# placa_para_insolar_joystick.net
KiCad netlist of a schematic drawn in EAGLE
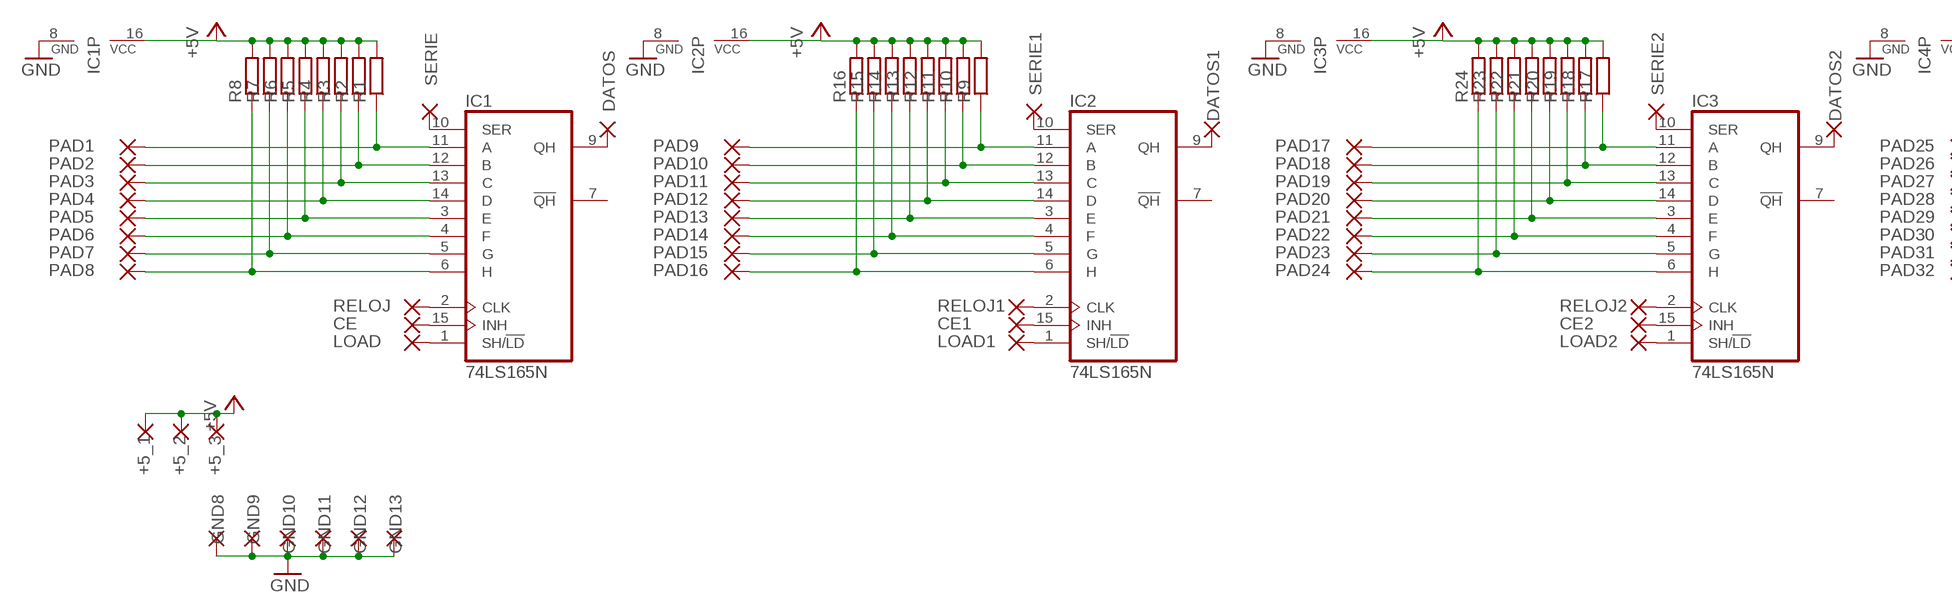
[diagram p0: schematic, sheet 1, part 1 of 2]
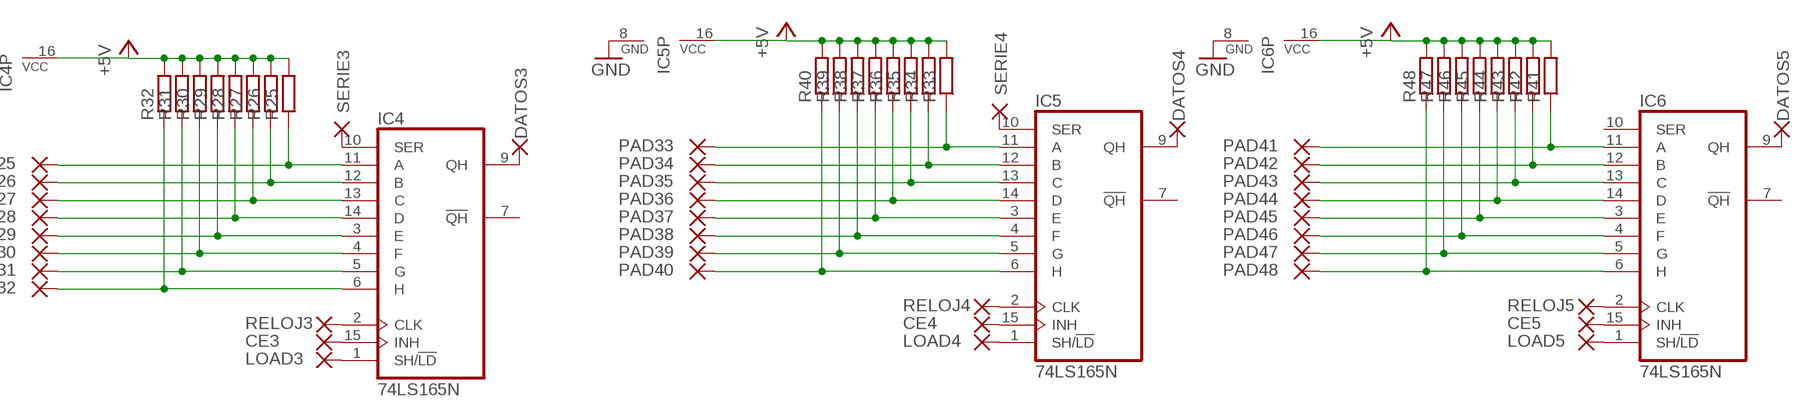
[diagram p1: schematic, sheet 1, part 2 of 2]

(export (version "E")
  (design (tool "Eeschema 10.0.6"))
  (components
    (comp (ref "+5_1")
      (value "WIREPAD2,54/1,0")
      (footprint "eagle-import:2,54_1,0")
      (libsource (lib "eagle-import") (part "WIREPAD2,54/1,0"))
    )
    (comp (ref "+5_2")
      (value "WIREPAD2,54/1,0")
      (footprint "eagle-import:2,54_1,0")
      (libsource (lib "eagle-import") (part "WIREPAD2,54/1,0"))
    )
    (comp (ref "+5_3")
      (value "WIREPAD2,54/1,0")
      (footprint "eagle-import:2,54_1,0")
      (libsource (lib "eagle-import") (part "WIREPAD2,54/1,0"))
    )
    (comp (ref "CE")
      (value "WIREPAD2,54/1,0")
      (footprint "eagle-import:2,54_1,0")
      (libsource (lib "eagle-import") (part "WIREPAD2,54/1,0"))
    )
    (comp (ref "CE1")
      (value "WIREPAD2,54/1,0")
      (footprint "eagle-import:2,54_1,0")
      (libsource (lib "eagle-import") (part "WIREPAD2,54/1,0"))
    )
    (comp (ref "CE2")
      (value "WIREPAD2,54/1,0")
      (footprint "eagle-import:2,54_1,0")
      (libsource (lib "eagle-import") (part "WIREPAD2,54/1,0"))
    )
    (comp (ref "CE3")
      (value "WIREPAD2,54/1,0")
      (footprint "eagle-import:2,54_1,0")
      (libsource (lib "eagle-import") (part "WIREPAD2,54/1,0"))
    )
    (comp (ref "CE4")
      (value "WIREPAD2,54/1,0")
      (footprint "eagle-import:2,54_1,0")
      (libsource (lib "eagle-import") (part "WIREPAD2,54/1,0"))
    )
    (comp (ref "CE5")
      (value "WIREPAD2,54/1,0")
      (footprint "eagle-import:2,54_1,0")
      (libsource (lib "eagle-import") (part "WIREPAD2,54/1,0"))
    )
    (comp (ref "DATOS")
      (value "WIREPAD2,54/1,0")
      (footprint "eagle-import:2,54_1,0")
      (libsource (lib "eagle-import") (part "WIREPAD2,54/1,0"))
    )
    (comp (ref "DATOS1")
      (value "WIREPAD2,54/1,0")
      (footprint "eagle-import:2,54_1,0")
      (libsource (lib "eagle-import") (part "WIREPAD2,54/1,0"))
    )
    (comp (ref "DATOS2")
      (value "WIREPAD2,54/1,0")
      (footprint "eagle-import:2,54_1,0")
      (libsource (lib "eagle-import") (part "WIREPAD2,54/1,0"))
    )
    (comp (ref "DATOS3")
      (value "WIREPAD2,54/1,0")
      (footprint "eagle-import:2,54_1,0")
      (libsource (lib "eagle-import") (part "WIREPAD2,54/1,0"))
    )
    (comp (ref "DATOS4")
      (value "WIREPAD2,54/1,0")
      (footprint "eagle-import:2,54_1,0")
      (libsource (lib "eagle-import") (part "WIREPAD2,54/1,0"))
    )
    (comp (ref "DATOS5")
      (value "WIREPAD2,54/1,0")
      (footprint "eagle-import:2,54_1,0")
      (libsource (lib "eagle-import") (part "WIREPAD2,54/1,0"))
    )
    (comp (ref "GND8")
      (value "WIREPAD2,54/1,0")
      (footprint "eagle-import:2,54_1,0")
      (libsource (lib "eagle-import") (part "WIREPAD2,54/1,0"))
    )
    (comp (ref "GND9")
      (value "WIREPAD2,54/1,0")
      (footprint "eagle-import:2,54_1,0")
      (libsource (lib "eagle-import") (part "WIREPAD2,54/1,0"))
    )
    (comp (ref "GND10")
      (value "WIREPAD2,54/1,0")
      (footprint "eagle-import:2,54_1,0")
      (libsource (lib "eagle-import") (part "WIREPAD2,54/1,0"))
    )
    (comp (ref "GND11")
      (value "WIREPAD2,54/1,0")
      (footprint "eagle-import:2,54_1,0")
      (libsource (lib "eagle-import") (part "WIREPAD2,54/1,0"))
    )
    (comp (ref "GND12")
      (value "WIREPAD2,54/1,0")
      (footprint "eagle-import:2,54_1,0")
      (libsource (lib "eagle-import") (part "WIREPAD2,54/1,0"))
    )
    (comp (ref "GND13")
      (value "WIREPAD2,54/1,0")
      (footprint "eagle-import:2,54_1,0")
      (libsource (lib "eagle-import") (part "WIREPAD2,54/1,0"))
    )
    (comp (ref "IC1")
      (value "74LS165N")
      (footprint "eagle-import:DIL16")
      (libsource (lib "eagle-import") (part "74165NLS"))
    )
    (comp (ref "IC2")
      (value "74LS165N")
      (footprint "eagle-import:DIL16")
      (libsource (lib "eagle-import") (part "74165NLS"))
    )
    (comp (ref "IC3")
      (value "74LS165N")
      (footprint "eagle-import:DIL16")
      (libsource (lib "eagle-import") (part "74165NLS"))
    )
    (comp (ref "IC4")
      (value "74LS165N")
      (footprint "eagle-import:DIL16")
      (libsource (lib "eagle-import") (part "74165NLS"))
    )
    (comp (ref "IC5")
      (value "74LS165N")
      (footprint "eagle-import:DIL16")
      (libsource (lib "eagle-import") (part "74165NLS"))
    )
    (comp (ref "IC6")
      (value "74LS165N")
      (footprint "eagle-import:DIL16")
      (libsource (lib "eagle-import") (part "74165NLS"))
    )
    (comp (ref "LOAD")
      (value "WIREPAD2,54/1,0")
      (footprint "eagle-import:2,54_1,0")
      (libsource (lib "eagle-import") (part "WIREPAD2,54/1,0"))
    )
    (comp (ref "LOAD1")
      (value "WIREPAD2,54/1,0")
      (footprint "eagle-import:2,54_1,0")
      (libsource (lib "eagle-import") (part "WIREPAD2,54/1,0"))
    )
    (comp (ref "LOAD2")
      (value "WIREPAD2,54/1,0")
      (footprint "eagle-import:2,54_1,0")
      (libsource (lib "eagle-import") (part "WIREPAD2,54/1,0"))
    )
    (comp (ref "LOAD3")
      (value "WIREPAD2,54/1,0")
      (footprint "eagle-import:2,54_1,0")
      (libsource (lib "eagle-import") (part "WIREPAD2,54/1,0"))
    )
    (comp (ref "LOAD4")
      (value "WIREPAD2,54/1,0")
      (footprint "eagle-import:2,54_1,0")
      (libsource (lib "eagle-import") (part "WIREPAD2,54/1,0"))
    )
    (comp (ref "LOAD5")
      (value "WIREPAD2,54/1,0")
      (footprint "eagle-import:2,54_1,0")
      (libsource (lib "eagle-import") (part "WIREPAD2,54/1,0"))
    )
    (comp (ref "PAD1")
      (value "WIREPAD2,54/1,0")
      (footprint "eagle-import:2,54_1,0")
      (libsource (lib "eagle-import") (part "WIREPAD2,54/1,0"))
    )
    (comp (ref "PAD2")
      (value "WIREPAD2,54/1,0")
      (footprint "eagle-import:2,54_1,0")
      (libsource (lib "eagle-import") (part "WIREPAD2,54/1,0"))
    )
    (comp (ref "PAD3")
      (value "WIREPAD2,54/1,0")
      (footprint "eagle-import:2,54_1,0")
      (libsource (lib "eagle-import") (part "WIREPAD2,54/1,0"))
    )
    (comp (ref "PAD4")
      (value "WIREPAD2,54/1,0")
      (footprint "eagle-import:2,54_1,0")
      (libsource (lib "eagle-import") (part "WIREPAD2,54/1,0"))
    )
    (comp (ref "PAD5")
      (value "WIREPAD2,54/1,0")
      (footprint "eagle-import:2,54_1,0")
      (libsource (lib "eagle-import") (part "WIREPAD2,54/1,0"))
    )
    (comp (ref "PAD6")
      (value "WIREPAD2,54/1,0")
      (footprint "eagle-import:2,54_1,0")
      (libsource (lib "eagle-import") (part "WIREPAD2,54/1,0"))
    )
    (comp (ref "PAD7")
      (value "WIREPAD2,54/1,0")
      (footprint "eagle-import:2,54_1,0")
      (libsource (lib "eagle-import") (part "WIREPAD2,54/1,0"))
    )
    (comp (ref "PAD8")
      (value "WIREPAD2,54/1,0")
      (footprint "eagle-import:2,54_1,0")
      (libsource (lib "eagle-import") (part "WIREPAD2,54/1,0"))
    )
    (comp (ref "PAD9")
      (value "WIREPAD2,54/1,0")
      (footprint "eagle-import:2,54_1,0")
      (libsource (lib "eagle-import") (part "WIREPAD2,54/1,0"))
    )
    (comp (ref "PAD10")
      (value "WIREPAD2,54/1,0")
      (footprint "eagle-import:2,54_1,0")
      (libsource (lib "eagle-import") (part "WIREPAD2,54/1,0"))
    )
    (comp (ref "PAD11")
      (value "WIREPAD2,54/1,0")
      (footprint "eagle-import:2,54_1,0")
      (libsource (lib "eagle-import") (part "WIREPAD2,54/1,0"))
    )
    (comp (ref "PAD12")
      (value "WIREPAD2,54/1,0")
      (footprint "eagle-import:2,54_1,0")
      (libsource (lib "eagle-import") (part "WIREPAD2,54/1,0"))
    )
    (comp (ref "PAD13")
      (value "WIREPAD2,54/1,0")
      (footprint "eagle-import:2,54_1,0")
      (libsource (lib "eagle-import") (part "WIREPAD2,54/1,0"))
    )
    (comp (ref "PAD14")
      (value "WIREPAD2,54/1,0")
      (footprint "eagle-import:2,54_1,0")
      (libsource (lib "eagle-import") (part "WIREPAD2,54/1,0"))
    )
    (comp (ref "PAD15")
      (value "WIREPAD2,54/1,0")
      (footprint "eagle-import:2,54_1,0")
      (libsource (lib "eagle-import") (part "WIREPAD2,54/1,0"))
    )
    (comp (ref "PAD16")
      (value "WIREPAD2,54/1,0")
      (footprint "eagle-import:2,54_1,0")
      (libsource (lib "eagle-import") (part "WIREPAD2,54/1,0"))
    )
    (comp (ref "PAD17")
      (value "WIREPAD2,54/1,0")
      (footprint "eagle-import:2,54_1,0")
      (libsource (lib "eagle-import") (part "WIREPAD2,54/1,0"))
    )
    (comp (ref "PAD18")
      (value "WIREPAD2,54/1,0")
      (footprint "eagle-import:2,54_1,0")
      (libsource (lib "eagle-import") (part "WIREPAD2,54/1,0"))
    )
    (comp (ref "PAD19")
      (value "WIREPAD2,54/1,0")
      (footprint "eagle-import:2,54_1,0")
      (libsource (lib "eagle-import") (part "WIREPAD2,54/1,0"))
    )
    (comp (ref "PAD20")
      (value "WIREPAD2,54/1,0")
      (footprint "eagle-import:2,54_1,0")
      (libsource (lib "eagle-import") (part "WIREPAD2,54/1,0"))
    )
    (comp (ref "PAD21")
      (value "WIREPAD2,54/1,0")
      (footprint "eagle-import:2,54_1,0")
      (libsource (lib "eagle-import") (part "WIREPAD2,54/1,0"))
    )
    (comp (ref "PAD22")
      (value "WIREPAD2,54/1,0")
      (footprint "eagle-import:2,54_1,0")
      (libsource (lib "eagle-import") (part "WIREPAD2,54/1,0"))
    )
    (comp (ref "PAD23")
      (value "WIREPAD2,54/1,0")
      (footprint "eagle-import:2,54_1,0")
      (libsource (lib "eagle-import") (part "WIREPAD2,54/1,0"))
    )
    (comp (ref "PAD24")
      (value "WIREPAD2,54/1,0")
      (footprint "eagle-import:2,54_1,0")
      (libsource (lib "eagle-import") (part "WIREPAD2,54/1,0"))
    )
    (comp (ref "PAD25")
      (value "WIREPAD2,54/1,0")
      (footprint "eagle-import:2,54_1,0")
      (libsource (lib "eagle-import") (part "WIREPAD2,54/1,0"))
    )
    (comp (ref "PAD26")
      (value "WIREPAD2,54/1,0")
      (footprint "eagle-import:2,54_1,0")
      (libsource (lib "eagle-import") (part "WIREPAD2,54/1,0"))
    )
    (comp (ref "PAD27")
      (value "WIREPAD2,54/1,0")
      (footprint "eagle-import:2,54_1,0")
      (libsource (lib "eagle-import") (part "WIREPAD2,54/1,0"))
    )
    (comp (ref "PAD28")
      (value "WIREPAD2,54/1,0")
      (footprint "eagle-import:2,54_1,0")
      (libsource (lib "eagle-import") (part "WIREPAD2,54/1,0"))
    )
    (comp (ref "PAD29")
      (value "WIREPAD2,54/1,0")
      (footprint "eagle-import:2,54_1,0")
      (libsource (lib "eagle-import") (part "WIREPAD2,54/1,0"))
    )
    (comp (ref "PAD30")
      (value "WIREPAD2,54/1,0")
      (footprint "eagle-import:2,54_1,0")
      (libsource (lib "eagle-import") (part "WIREPAD2,54/1,0"))
    )
    (comp (ref "PAD31")
      (value "WIREPAD2,54/1,0")
      (footprint "eagle-import:2,54_1,0")
      (libsource (lib "eagle-import") (part "WIREPAD2,54/1,0"))
    )
    (comp (ref "PAD32")
      (value "WIREPAD2,54/1,0")
      (footprint "eagle-import:2,54_1,0")
      (libsource (lib "eagle-import") (part "WIREPAD2,54/1,0"))
    )
    (comp (ref "PAD33")
      (value "WIREPAD2,54/1,0")
      (footprint "eagle-import:2,54_1,0")
      (libsource (lib "eagle-import") (part "WIREPAD2,54/1,0"))
    )
    (comp (ref "PAD34")
      (value "WIREPAD2,54/1,0")
      (footprint "eagle-import:2,54_1,0")
      (libsource (lib "eagle-import") (part "WIREPAD2,54/1,0"))
    )
    (comp (ref "PAD35")
      (value "WIREPAD2,54/1,0")
      (footprint "eagle-import:2,54_1,0")
      (libsource (lib "eagle-import") (part "WIREPAD2,54/1,0"))
    )
    (comp (ref "PAD36")
      (value "WIREPAD2,54/1,0")
      (footprint "eagle-import:2,54_1,0")
      (libsource (lib "eagle-import") (part "WIREPAD2,54/1,0"))
    )
    (comp (ref "PAD37")
      (value "WIREPAD2,54/1,0")
      (footprint "eagle-import:2,54_1,0")
      (libsource (lib "eagle-import") (part "WIREPAD2,54/1,0"))
    )
    (comp (ref "PAD38")
      (value "WIREPAD2,54/1,0")
      (footprint "eagle-import:2,54_1,0")
      (libsource (lib "eagle-import") (part "WIREPAD2,54/1,0"))
    )
    (comp (ref "PAD39")
      (value "WIREPAD2,54/1,0")
      (footprint "eagle-import:2,54_1,0")
      (libsource (lib "eagle-import") (part "WIREPAD2,54/1,0"))
    )
    (comp (ref "PAD40")
      (value "WIREPAD2,54/1,0")
      (footprint "eagle-import:2,54_1,0")
      (libsource (lib "eagle-import") (part "WIREPAD2,54/1,0"))
    )
    (comp (ref "PAD41")
      (value "WIREPAD2,54/1,0")
      (footprint "eagle-import:2,54_1,0")
      (libsource (lib "eagle-import") (part "WIREPAD2,54/1,0"))
    )
    (comp (ref "PAD42")
      (value "WIREPAD2,54/1,0")
      (footprint "eagle-import:2,54_1,0")
      (libsource (lib "eagle-import") (part "WIREPAD2,54/1,0"))
    )
    (comp (ref "PAD43")
      (value "WIREPAD2,54/1,0")
      (footprint "eagle-import:2,54_1,0")
      (libsource (lib "eagle-import") (part "WIREPAD2,54/1,0"))
    )
    (comp (ref "PAD44")
      (value "WIREPAD2,54/1,0")
      (footprint "eagle-import:2,54_1,0")
      (libsource (lib "eagle-import") (part "WIREPAD2,54/1,0"))
    )
    (comp (ref "PAD45")
      (value "WIREPAD2,54/1,0")
      (footprint "eagle-import:2,54_1,0")
      (libsource (lib "eagle-import") (part "WIREPAD2,54/1,0"))
    )
    (comp (ref "PAD46")
      (value "WIREPAD2,54/1,0")
      (footprint "eagle-import:2,54_1,0")
      (libsource (lib "eagle-import") (part "WIREPAD2,54/1,0"))
    )
    (comp (ref "PAD47")
      (value "WIREPAD2,54/1,0")
      (footprint "eagle-import:2,54_1,0")
      (libsource (lib "eagle-import") (part "WIREPAD2,54/1,0"))
    )
    (comp (ref "PAD48")
      (value "WIREPAD2,54/1,0")
      (footprint "eagle-import:2,54_1,0")
      (libsource (lib "eagle-import") (part "WIREPAD2,54/1,0"))
    )
    (comp (ref "R1")
      (value "R-EU_0204/7")
      (footprint "eagle-import:0204_7")
      (libsource (lib "eagle-import") (part "R-EU_0204/7"))
    )
    (comp (ref "R2")
      (value "R-EU_0204/7")
      (footprint "eagle-import:0204_7")
      (libsource (lib "eagle-import") (part "R-EU_0204/7"))
    )
    (comp (ref "R3")
      (value "R-EU_0204/7")
      (footprint "eagle-import:0204_7")
      (libsource (lib "eagle-import") (part "R-EU_0204/7"))
    )
    (comp (ref "R4")
      (value "R-EU_0204/7")
      (footprint "eagle-import:0204_7")
      (libsource (lib "eagle-import") (part "R-EU_0204/7"))
    )
    (comp (ref "R5")
      (value "R-EU_0204/7")
      (footprint "eagle-import:0204_7")
      (libsource (lib "eagle-import") (part "R-EU_0204/7"))
    )
    (comp (ref "R6")
      (value "R-EU_0204/7")
      (footprint "eagle-import:0204_7")
      (libsource (lib "eagle-import") (part "R-EU_0204/7"))
    )
    (comp (ref "R7")
      (value "R-EU_0204/7")
      (footprint "eagle-import:0204_7")
      (libsource (lib "eagle-import") (part "R-EU_0204/7"))
    )
    (comp (ref "R8")
      (value "R-EU_0204/7")
      (footprint "eagle-import:0204_7")
      (libsource (lib "eagle-import") (part "R-EU_0204/7"))
    )
    (comp (ref "R9")
      (value "R-EU_0204/7")
      (footprint "eagle-import:0204_7")
      (libsource (lib "eagle-import") (part "R-EU_0204/7"))
    )
    (comp (ref "R10")
      (value "R-EU_0204/7")
      (footprint "eagle-import:0204_7")
      (libsource (lib "eagle-import") (part "R-EU_0204/7"))
    )
    (comp (ref "R11")
      (value "R-EU_0204/7")
      (footprint "eagle-import:0204_7")
      (libsource (lib "eagle-import") (part "R-EU_0204/7"))
    )
    (comp (ref "R12")
      (value "R-EU_0204/7")
      (footprint "eagle-import:0204_7")
      (libsource (lib "eagle-import") (part "R-EU_0204/7"))
    )
    (comp (ref "R13")
      (value "R-EU_0204/7")
      (footprint "eagle-import:0204_7")
      (libsource (lib "eagle-import") (part "R-EU_0204/7"))
    )
    (comp (ref "R14")
      (value "R-EU_0204/7")
      (footprint "eagle-import:0204_7")
      (libsource (lib "eagle-import") (part "R-EU_0204/7"))
    )
    (comp (ref "R15")
      (value "R-EU_0204/7")
      (footprint "eagle-import:0204_7")
      (libsource (lib "eagle-import") (part "R-EU_0204/7"))
    )
    (comp (ref "R16")
      (value "R-EU_0204/7")
      (footprint "eagle-import:0204_7")
      (libsource (lib "eagle-import") (part "R-EU_0204/7"))
    )
    (comp (ref "R17")
      (value "R-EU_0204/7")
      (footprint "eagle-import:0204_7")
      (libsource (lib "eagle-import") (part "R-EU_0204/7"))
    )
    (comp (ref "R18")
      (value "R-EU_0204/7")
      (footprint "eagle-import:0204_7")
      (libsource (lib "eagle-import") (part "R-EU_0204/7"))
    )
    (comp (ref "R19")
      (value "R-EU_0204/7")
      (footprint "eagle-import:0204_7")
      (libsource (lib "eagle-import") (part "R-EU_0204/7"))
    )
    (comp (ref "R20")
      (value "R-EU_0204/7")
      (footprint "eagle-import:0204_7")
      (libsource (lib "eagle-import") (part "R-EU_0204/7"))
    )
    (comp (ref "R21")
      (value "R-EU_0204/7")
      (footprint "eagle-import:0204_7")
      (libsource (lib "eagle-import") (part "R-EU_0204/7"))
    )
    (comp (ref "R22")
      (value "R-EU_0204/7")
      (footprint "eagle-import:0204_7")
      (libsource (lib "eagle-import") (part "R-EU_0204/7"))
    )
    (comp (ref "R23")
      (value "R-EU_0204/7")
      (footprint "eagle-import:0204_7")
      (libsource (lib "eagle-import") (part "R-EU_0204/7"))
    )
    (comp (ref "R24")
      (value "R-EU_0204/7")
      (footprint "eagle-import:0204_7")
      (libsource (lib "eagle-import") (part "R-EU_0204/7"))
    )
    (comp (ref "R25")
      (value "R-EU_0204/7")
      (footprint "eagle-import:0204_7")
      (libsource (lib "eagle-import") (part "R-EU_0204/7"))
    )
    (comp (ref "R26")
      (value "R-EU_0204/7")
      (footprint "eagle-import:0204_7")
      (libsource (lib "eagle-import") (part "R-EU_0204/7"))
    )
    (comp (ref "R27")
      (value "R-EU_0204/7")
      (footprint "eagle-import:0204_7")
      (libsource (lib "eagle-import") (part "R-EU_0204/7"))
    )
    (comp (ref "R28")
      (value "R-EU_0204/7")
      (footprint "eagle-import:0204_7")
      (libsource (lib "eagle-import") (part "R-EU_0204/7"))
    )
    (comp (ref "R29")
      (value "R-EU_0204/7")
      (footprint "eagle-import:0204_7")
      (libsource (lib "eagle-import") (part "R-EU_0204/7"))
    )
    (comp (ref "R30")
      (value "R-EU_0204/7")
      (footprint "eagle-import:0204_7")
      (libsource (lib "eagle-import") (part "R-EU_0204/7"))
    )
    (comp (ref "R31")
      (value "R-EU_0204/7")
      (footprint "eagle-import:0204_7")
      (libsource (lib "eagle-import") (part "R-EU_0204/7"))
    )
    (comp (ref "R32")
      (value "R-EU_0204/7")
      (footprint "eagle-import:0204_7")
      (libsource (lib "eagle-import") (part "R-EU_0204/7"))
    )
    (comp (ref "R33")
      (value "R-EU_0204/7")
      (footprint "eagle-import:0204_7")
      (libsource (lib "eagle-import") (part "R-EU_0204/7"))
    )
    (comp (ref "R34")
      (value "R-EU_0204/7")
      (footprint "eagle-import:0204_7")
      (libsource (lib "eagle-import") (part "R-EU_0204/7"))
    )
    (comp (ref "R35")
      (value "R-EU_0204/7")
      (footprint "eagle-import:0204_7")
      (libsource (lib "eagle-import") (part "R-EU_0204/7"))
    )
    (comp (ref "R36")
      (value "R-EU_0204/7")
      (footprint "eagle-import:0204_7")
      (libsource (lib "eagle-import") (part "R-EU_0204/7"))
    )
    (comp (ref "R37")
      (value "R-EU_0204/7")
      (footprint "eagle-import:0204_7")
      (libsource (lib "eagle-import") (part "R-EU_0204/7"))
    )
    (comp (ref "R38")
      (value "R-EU_0204/7")
      (footprint "eagle-import:0204_7")
      (libsource (lib "eagle-import") (part "R-EU_0204/7"))
    )
    (comp (ref "R39")
      (value "R-EU_0204/7")
      (footprint "eagle-import:0204_7")
      (libsource (lib "eagle-import") (part "R-EU_0204/7"))
    )
    (comp (ref "R40")
      (value "R-EU_0204/7")
      (footprint "eagle-import:0204_7")
      (libsource (lib "eagle-import") (part "R-EU_0204/7"))
    )
    (comp (ref "R41")
      (value "R-EU_0204/7")
      (footprint "eagle-import:0204_7")
      (libsource (lib "eagle-import") (part "R-EU_0204/7"))
    )
    (comp (ref "R42")
      (value "R-EU_0204/7")
      (footprint "eagle-import:0204_7")
      (libsource (lib "eagle-import") (part "R-EU_0204/7"))
    )
    (comp (ref "R43")
      (value "R-EU_0204/7")
      (footprint "eagle-import:0204_7")
      (libsource (lib "eagle-import") (part "R-EU_0204/7"))
    )
    (comp (ref "R44")
      (value "R-EU_0204/7")
      (footprint "eagle-import:0204_7")
      (libsource (lib "eagle-import") (part "R-EU_0204/7"))
    )
    (comp (ref "R45")
      (value "R-EU_0204/7")
      (footprint "eagle-import:0204_7")
      (libsource (lib "eagle-import") (part "R-EU_0204/7"))
    )
    (comp (ref "R46")
      (value "R-EU_0204/7")
      (footprint "eagle-import:0204_7")
      (libsource (lib "eagle-import") (part "R-EU_0204/7"))
    )
    (comp (ref "R47")
      (value "R-EU_0204/7")
      (footprint "eagle-import:0204_7")
      (libsource (lib "eagle-import") (part "R-EU_0204/7"))
    )
    (comp (ref "R48")
      (value "R-EU_0204/7")
      (footprint "eagle-import:0204_7")
      (libsource (lib "eagle-import") (part "R-EU_0204/7"))
    )
    (comp (ref "RELOJ")
      (value "WIREPAD2,54/1,0")
      (footprint "eagle-import:2,54_1,0")
      (libsource (lib "eagle-import") (part "WIREPAD2,54/1,0"))
    )
    (comp (ref "RELOJ1")
      (value "WIREPAD2,54/1,0")
      (footprint "eagle-import:2,54_1,0")
      (libsource (lib "eagle-import") (part "WIREPAD2,54/1,0"))
    )
    (comp (ref "RELOJ2")
      (value "WIREPAD2,54/1,0")
      (footprint "eagle-import:2,54_1,0")
      (libsource (lib "eagle-import") (part "WIREPAD2,54/1,0"))
    )
    (comp (ref "RELOJ3")
      (value "WIREPAD2,54/1,0")
      (footprint "eagle-import:2,54_1,0")
      (libsource (lib "eagle-import") (part "WIREPAD2,54/1,0"))
    )
    (comp (ref "RELOJ4")
      (value "WIREPAD2,54/1,0")
      (footprint "eagle-import:2,54_1,0")
      (libsource (lib "eagle-import") (part "WIREPAD2,54/1,0"))
    )
    (comp (ref "RELOJ5")
      (value "WIREPAD2,54/1,0")
      (footprint "eagle-import:2,54_1,0")
      (libsource (lib "eagle-import") (part "WIREPAD2,54/1,0"))
    )
    (comp (ref "SERIE")
      (value "WIREPAD2,54/1,0")
      (footprint "eagle-import:2,54_1,0")
      (libsource (lib "eagle-import") (part "WIREPAD2,54/1,0"))
    )
    (comp (ref "SERIE1")
      (value "WIREPAD2,54/1,0")
      (footprint "eagle-import:2,54_1,0")
      (libsource (lib "eagle-import") (part "WIREPAD2,54/1,0"))
    )
    (comp (ref "SERIE2")
      (value "WIREPAD2,54/1,0")
      (footprint "eagle-import:2,54_1,0")
      (libsource (lib "eagle-import") (part "WIREPAD2,54/1,0"))
    )
    (comp (ref "SERIE3")
      (value "WIREPAD2,54/1,0")
      (footprint "eagle-import:2,54_1,0")
      (libsource (lib "eagle-import") (part "WIREPAD2,54/1,0"))
    )
    (comp (ref "SERIE4")
      (value "WIREPAD2,54/1,0")
      (footprint "eagle-import:2,54_1,0")
      (libsource (lib "eagle-import") (part "WIREPAD2,54/1,0"))
    )
  )
  (nets
    (net (code "1") (name "+5V") (class "Default")
      (node (ref "+5_1") (pin "1") (pinfunction "P_1") (pintype "passive"))
      (node (ref "+5_2") (pin "1") (pinfunction "P_1") (pintype "passive"))
      (node (ref "+5_3") (pin "1") (pinfunction "P_1") (pintype "passive"))
      (node (ref "IC1") (pin "16") (pinfunction "VCC_16") (pintype "power_in"))
      (node (ref "IC2") (pin "16") (pinfunction "VCC_16") (pintype "power_in"))
      (node (ref "IC3") (pin "16") (pinfunction "VCC_16") (pintype "power_in"))
      (node (ref "IC4") (pin "16") (pinfunction "VCC_16") (pintype "power_in"))
      (node (ref "IC5") (pin "16") (pinfunction "VCC_16") (pintype "power_in"))
      (node (ref "IC6") (pin "16") (pinfunction "VCC_16") (pintype "power_in"))
      (node (ref "R1") (pin "2") (pinfunction "2_2") (pintype "passive"))
      (node (ref "R10") (pin "2") (pinfunction "2_2") (pintype "passive"))
      (node (ref "R11") (pin "2") (pinfunction "2_2") (pintype "passive"))
      (node (ref "R12") (pin "2") (pinfunction "2_2") (pintype "passive"))
      (node (ref "R13") (pin "2") (pinfunction "2_2") (pintype "passive"))
      (node (ref "R14") (pin "2") (pinfunction "2_2") (pintype "passive"))
      (node (ref "R15") (pin "2") (pinfunction "2_2") (pintype "passive"))
      (node (ref "R16") (pin "2") (pinfunction "2_2") (pintype "passive"))
      (node (ref "R17") (pin "2") (pinfunction "2_2") (pintype "passive"))
      (node (ref "R18") (pin "2") (pinfunction "2_2") (pintype "passive"))
      (node (ref "R19") (pin "2") (pinfunction "2_2") (pintype "passive"))
      (node (ref "R2") (pin "2") (pinfunction "2_2") (pintype "passive"))
      (node (ref "R20") (pin "2") (pinfunction "2_2") (pintype "passive"))
      (node (ref "R21") (pin "2") (pinfunction "2_2") (pintype "passive"))
      (node (ref "R22") (pin "2") (pinfunction "2_2") (pintype "passive"))
      (node (ref "R23") (pin "2") (pinfunction "2_2") (pintype "passive"))
      (node (ref "R24") (pin "2") (pinfunction "2_2") (pintype "passive"))
      (node (ref "R25") (pin "2") (pinfunction "2_2") (pintype "passive"))
      (node (ref "R26") (pin "2") (pinfunction "2_2") (pintype "passive"))
      (node (ref "R27") (pin "2") (pinfunction "2_2") (pintype "passive"))
      (node (ref "R28") (pin "2") (pinfunction "2_2") (pintype "passive"))
      (node (ref "R29") (pin "2") (pinfunction "2_2") (pintype "passive"))
      (node (ref "R3") (pin "2") (pinfunction "2_2") (pintype "passive"))
      (node (ref "R30") (pin "2") (pinfunction "2_2") (pintype "passive"))
      (node (ref "R31") (pin "2") (pinfunction "2_2") (pintype "passive"))
      (node (ref "R32") (pin "2") (pinfunction "2_2") (pintype "passive"))
      (node (ref "R33") (pin "2") (pinfunction "2_2") (pintype "passive"))
      (node (ref "R34") (pin "2") (pinfunction "2_2") (pintype "passive"))
      (node (ref "R35") (pin "2") (pinfunction "2_2") (pintype "passive"))
      (node (ref "R36") (pin "2") (pinfunction "2_2") (pintype "passive"))
      (node (ref "R37") (pin "2") (pinfunction "2_2") (pintype "passive"))
      (node (ref "R38") (pin "2") (pinfunction "2_2") (pintype "passive"))
      (node (ref "R39") (pin "2") (pinfunction "2_2") (pintype "passive"))
      (node (ref "R4") (pin "2") (pinfunction "2_2") (pintype "passive"))
      (node (ref "R40") (pin "2") (pinfunction "2_2") (pintype "passive"))
      (node (ref "R41") (pin "2") (pinfunction "2_2") (pintype "passive"))
      (node (ref "R42") (pin "2") (pinfunction "2_2") (pintype "passive"))
      (node (ref "R43") (pin "2") (pinfunction "2_2") (pintype "passive"))
      (node (ref "R44") (pin "2") (pinfunction "2_2") (pintype "passive"))
      (node (ref "R45") (pin "2") (pinfunction "2_2") (pintype "passive"))
      (node (ref "R46") (pin "2") (pinfunction "2_2") (pintype "passive"))
      (node (ref "R47") (pin "2") (pinfunction "2_2") (pintype "passive"))
      (node (ref "R48") (pin "2") (pinfunction "2_2") (pintype "passive"))
      (node (ref "R5") (pin "2") (pinfunction "2_2") (pintype "passive"))
      (node (ref "R6") (pin "2") (pinfunction "2_2") (pintype "passive"))
      (node (ref "R7") (pin "2") (pinfunction "2_2") (pintype "passive"))
      (node (ref "R8") (pin "2") (pinfunction "2_2") (pintype "passive"))
      (node (ref "R9") (pin "2") (pinfunction "2_2") (pintype "passive"))
    )
    (net (code "2") (name "GND") (class "Default")
      (node (ref "GND10") (pin "1") (pinfunction "P_1") (pintype "passive"))
      (node (ref "GND11") (pin "1") (pinfunction "P_1") (pintype "passive"))
      (node (ref "GND12") (pin "1") (pinfunction "P_1") (pintype "passive"))
      (node (ref "GND13") (pin "1") (pinfunction "P_1") (pintype "passive"))
      (node (ref "GND8") (pin "1") (pinfunction "P_1") (pintype "passive"))
      (node (ref "GND9") (pin "1") (pinfunction "P_1") (pintype "passive"))
      (node (ref "IC1") (pin "8") (pinfunction "GND_8") (pintype "power_in"))
      (node (ref "IC2") (pin "8") (pinfunction "GND_8") (pintype "power_in"))
      (node (ref "IC3") (pin "8") (pinfunction "GND_8") (pintype "power_in"))
      (node (ref "IC4") (pin "8") (pinfunction "GND_8") (pintype "power_in"))
      (node (ref "IC5") (pin "8") (pinfunction "GND_8") (pintype "power_in"))
      (node (ref "IC6") (pin "8") (pinfunction "GND_8") (pintype "power_in"))
    )
    (net (code "3") (name "Net-(CE-P)") (class "Default")
      (node (ref "CE") (pin "1") (pinfunction "P_1") (pintype "passive"))
      (node (ref "IC1") (pin "15") (pinfunction "INH_15") (pintype "input"))
    )
    (net (code "4") (name "Net-(CE1-P)") (class "Default")
      (node (ref "CE1") (pin "1") (pinfunction "P_1") (pintype "passive"))
      (node (ref "IC2") (pin "15") (pinfunction "INH_15") (pintype "input"))
    )
    (net (code "5") (name "Net-(CE2-P)") (class "Default")
      (node (ref "CE2") (pin "1") (pinfunction "P_1") (pintype "passive"))
      (node (ref "IC3") (pin "15") (pinfunction "INH_15") (pintype "input"))
    )
    (net (code "6") (name "Net-(CE3-P)") (class "Default")
      (node (ref "CE3") (pin "1") (pinfunction "P_1") (pintype "passive"))
      (node (ref "IC4") (pin "15") (pinfunction "INH_15") (pintype "input"))
    )
    (net (code "7") (name "Net-(CE4-P)") (class "Default")
      (node (ref "CE4") (pin "1") (pinfunction "P_1") (pintype "passive"))
      (node (ref "IC5") (pin "15") (pinfunction "INH_15") (pintype "input"))
    )
    (net (code "8") (name "Net-(CE5-P)") (class "Default")
      (node (ref "CE5") (pin "1") (pinfunction "P_1") (pintype "passive"))
      (node (ref "IC6") (pin "15") (pinfunction "INH_15") (pintype "input"))
    )
    (net (code "9") (name "Net-(DATOS-P)") (class "Default")
      (node (ref "DATOS") (pin "1") (pinfunction "P_1") (pintype "passive"))
      (node (ref "IC1") (pin "9") (pinfunction "QH_9") (pintype "output"))
    )
    (net (code "10") (name "Net-(DATOS1-P)") (class "Default")
      (node (ref "DATOS1") (pin "1") (pinfunction "P_1") (pintype "passive"))
      (node (ref "IC2") (pin "9") (pinfunction "QH_9") (pintype "output"))
    )
    (net (code "11") (name "Net-(DATOS2-P)") (class "Default")
      (node (ref "DATOS2") (pin "1") (pinfunction "P_1") (pintype "passive"))
      (node (ref "IC3") (pin "9") (pinfunction "QH_9") (pintype "output"))
    )
    (net (code "12") (name "Net-(DATOS3-P)") (class "Default")
      (node (ref "DATOS3") (pin "1") (pinfunction "P_1") (pintype "passive"))
      (node (ref "IC4") (pin "9") (pinfunction "QH_9") (pintype "output"))
    )
    (net (code "13") (name "Net-(DATOS4-P)") (class "Default")
      (node (ref "DATOS4") (pin "1") (pinfunction "P_1") (pintype "passive"))
      (node (ref "IC5") (pin "9") (pinfunction "QH_9") (pintype "output"))
    )
    (net (code "14") (name "Net-(DATOS5-P)") (class "Default")
      (node (ref "DATOS5") (pin "1") (pinfunction "P_1") (pintype "passive"))
      (node (ref "IC6") (pin "9") (pinfunction "QH_9") (pintype "output"))
    )
    (net (code "15") (name "Net-(IC1A-A)") (class "Default")
      (node (ref "IC1") (pin "11") (pinfunction "A_11") (pintype "input"))
      (node (ref "PAD1") (pin "1") (pinfunction "P_1") (pintype "passive"))
      (node (ref "R1") (pin "1") (pinfunction "1_1") (pintype "passive"))
    )
    (net (code "16") (name "Net-(IC1A-B)") (class "Default")
      (node (ref "IC1") (pin "12") (pinfunction "B_12") (pintype "input"))
      (node (ref "PAD2") (pin "1") (pinfunction "P_1") (pintype "passive"))
      (node (ref "R2") (pin "1") (pinfunction "1_1") (pintype "passive"))
    )
    (net (code "17") (name "Net-(IC1A-C)") (class "Default")
      (node (ref "IC1") (pin "13") (pinfunction "C_13") (pintype "input"))
      (node (ref "PAD3") (pin "1") (pinfunction "P_1") (pintype "passive"))
      (node (ref "R3") (pin "1") (pinfunction "1_1") (pintype "passive"))
    )
    (net (code "18") (name "Net-(IC1A-CLK)") (class "Default")
      (node (ref "IC1") (pin "2") (pinfunction "CLK_2") (pintype "input"))
      (node (ref "RELOJ") (pin "1") (pinfunction "P_1") (pintype "passive"))
    )
    (net (code "19") (name "Net-(IC1A-D)") (class "Default")
      (node (ref "IC1") (pin "14") (pinfunction "D_14") (pintype "input"))
      (node (ref "PAD4") (pin "1") (pinfunction "P_1") (pintype "passive"))
      (node (ref "R4") (pin "1") (pinfunction "1_1") (pintype "passive"))
    )
    (net (code "20") (name "Net-(IC1A-E)") (class "Default")
      (node (ref "IC1") (pin "3") (pinfunction "E_3") (pintype "input"))
      (node (ref "PAD5") (pin "1") (pinfunction "P_1") (pintype "passive"))
      (node (ref "R5") (pin "1") (pinfunction "1_1") (pintype "passive"))
    )
    (net (code "21") (name "Net-(IC1A-F)") (class "Default")
      (node (ref "IC1") (pin "4") (pinfunction "F_4") (pintype "input"))
      (node (ref "PAD6") (pin "1") (pinfunction "P_1") (pintype "passive"))
      (node (ref "R6") (pin "1") (pinfunction "1_1") (pintype "passive"))
    )
    (net (code "22") (name "Net-(IC1A-G)") (class "Default")
      (node (ref "IC1") (pin "5") (pinfunction "G_5") (pintype "input"))
      (node (ref "PAD7") (pin "1") (pinfunction "P_1") (pintype "passive"))
      (node (ref "R7") (pin "1") (pinfunction "1_1") (pintype "passive"))
    )
    (net (code "23") (name "Net-(IC1A-H)") (class "Default")
      (node (ref "IC1") (pin "6") (pinfunction "H_6") (pintype "input"))
      (node (ref "PAD8") (pin "1") (pinfunction "P_1") (pintype "passive"))
      (node (ref "R8") (pin "1") (pinfunction "1_1") (pintype "passive"))
    )
    (net (code "24") (name "Net-(IC1A-SER)") (class "Default")
      (node (ref "IC1") (pin "10") (pinfunction "SER_10") (pintype "input"))
      (node (ref "SERIE") (pin "1") (pinfunction "P_1") (pintype "passive"))
    )
    (net (code "25") (name "Net-(IC1A-SH{slash}~{LD})") (class "Default")
      (node (ref "IC1") (pin "1") (pinfunction "SH/~{LD}_1") (pintype "input"))
      (node (ref "LOAD") (pin "1") (pinfunction "P_1") (pintype "passive"))
    )
    (net (code "26") (name "Net-(IC2A-A)") (class "Default")
      (node (ref "IC2") (pin "11") (pinfunction "A_11") (pintype "input"))
      (node (ref "PAD9") (pin "1") (pinfunction "P_1") (pintype "passive"))
      (node (ref "R9") (pin "1") (pinfunction "1_1") (pintype "passive"))
    )
    (net (code "27") (name "Net-(IC2A-B)") (class "Default")
      (node (ref "IC2") (pin "12") (pinfunction "B_12") (pintype "input"))
      (node (ref "PAD10") (pin "1") (pinfunction "P_1") (pintype "passive"))
      (node (ref "R10") (pin "1") (pinfunction "1_1") (pintype "passive"))
    )
    (net (code "28") (name "Net-(IC2A-C)") (class "Default")
      (node (ref "IC2") (pin "13") (pinfunction "C_13") (pintype "input"))
      (node (ref "PAD11") (pin "1") (pinfunction "P_1") (pintype "passive"))
      (node (ref "R11") (pin "1") (pinfunction "1_1") (pintype "passive"))
    )
    (net (code "29") (name "Net-(IC2A-CLK)") (class "Default")
      (node (ref "IC2") (pin "2") (pinfunction "CLK_2") (pintype "input"))
      (node (ref "RELOJ1") (pin "1") (pinfunction "P_1") (pintype "passive"))
    )
    (net (code "30") (name "Net-(IC2A-D)") (class "Default")
      (node (ref "IC2") (pin "14") (pinfunction "D_14") (pintype "input"))
      (node (ref "PAD12") (pin "1") (pinfunction "P_1") (pintype "passive"))
      (node (ref "R12") (pin "1") (pinfunction "1_1") (pintype "passive"))
    )
    (net (code "31") (name "Net-(IC2A-E)") (class "Default")
      (node (ref "IC2") (pin "3") (pinfunction "E_3") (pintype "input"))
      (node (ref "PAD13") (pin "1") (pinfunction "P_1") (pintype "passive"))
      (node (ref "R13") (pin "1") (pinfunction "1_1") (pintype "passive"))
    )
    (net (code "32") (name "Net-(IC2A-F)") (class "Default")
      (node (ref "IC2") (pin "4") (pinfunction "F_4") (pintype "input"))
      (node (ref "PAD14") (pin "1") (pinfunction "P_1") (pintype "passive"))
      (node (ref "R14") (pin "1") (pinfunction "1_1") (pintype "passive"))
    )
    (net (code "33") (name "Net-(IC2A-G)") (class "Default")
      (node (ref "IC2") (pin "5") (pinfunction "G_5") (pintype "input"))
      (node (ref "PAD15") (pin "1") (pinfunction "P_1") (pintype "passive"))
      (node (ref "R15") (pin "1") (pinfunction "1_1") (pintype "passive"))
    )
    (net (code "34") (name "Net-(IC2A-H)") (class "Default")
      (node (ref "IC2") (pin "6") (pinfunction "H_6") (pintype "input"))
      (node (ref "PAD16") (pin "1") (pinfunction "P_1") (pintype "passive"))
      (node (ref "R16") (pin "1") (pinfunction "1_1") (pintype "passive"))
    )
    (net (code "35") (name "Net-(IC2A-SER)") (class "Default")
      (node (ref "IC2") (pin "10") (pinfunction "SER_10") (pintype "input"))
      (node (ref "SERIE1") (pin "1") (pinfunction "P_1") (pintype "passive"))
    )
    (net (code "36") (name "Net-(IC2A-SH{slash}~{LD})") (class "Default")
      (node (ref "IC2") (pin "1") (pinfunction "SH/~{LD}_1") (pintype "input"))
      (node (ref "LOAD1") (pin "1") (pinfunction "P_1") (pintype "passive"))
    )
    (net (code "37") (name "Net-(IC3A-A)") (class "Default")
      (node (ref "IC3") (pin "11") (pinfunction "A_11") (pintype "input"))
      (node (ref "PAD17") (pin "1") (pinfunction "P_1") (pintype "passive"))
      (node (ref "R17") (pin "1") (pinfunction "1_1") (pintype "passive"))
    )
    (net (code "38") (name "Net-(IC3A-B)") (class "Default")
      (node (ref "IC3") (pin "12") (pinfunction "B_12") (pintype "input"))
      (node (ref "PAD18") (pin "1") (pinfunction "P_1") (pintype "passive"))
      (node (ref "R18") (pin "1") (pinfunction "1_1") (pintype "passive"))
    )
    (net (code "39") (name "Net-(IC3A-C)") (class "Default")
      (node (ref "IC3") (pin "13") (pinfunction "C_13") (pintype "input"))
      (node (ref "PAD19") (pin "1") (pinfunction "P_1") (pintype "passive"))
      (node (ref "R19") (pin "1") (pinfunction "1_1") (pintype "passive"))
    )
    (net (code "40") (name "Net-(IC3A-CLK)") (class "Default")
      (node (ref "IC3") (pin "2") (pinfunction "CLK_2") (pintype "input"))
      (node (ref "RELOJ2") (pin "1") (pinfunction "P_1") (pintype "passive"))
    )
    (net (code "41") (name "Net-(IC3A-D)") (class "Default")
      (node (ref "IC3") (pin "14") (pinfunction "D_14") (pintype "input"))
      (node (ref "PAD20") (pin "1") (pinfunction "P_1") (pintype "passive"))
      (node (ref "R20") (pin "1") (pinfunction "1_1") (pintype "passive"))
    )
    (net (code "42") (name "Net-(IC3A-E)") (class "Default")
      (node (ref "IC3") (pin "3") (pinfunction "E_3") (pintype "input"))
      (node (ref "PAD21") (pin "1") (pinfunction "P_1") (pintype "passive"))
      (node (ref "R21") (pin "1") (pinfunction "1_1") (pintype "passive"))
    )
    (net (code "43") (name "Net-(IC3A-F)") (class "Default")
      (node (ref "IC3") (pin "4") (pinfunction "F_4") (pintype "input"))
      (node (ref "PAD22") (pin "1") (pinfunction "P_1") (pintype "passive"))
      (node (ref "R22") (pin "1") (pinfunction "1_1") (pintype "passive"))
    )
    (net (code "44") (name "Net-(IC3A-G)") (class "Default")
      (node (ref "IC3") (pin "5") (pinfunction "G_5") (pintype "input"))
      (node (ref "PAD23") (pin "1") (pinfunction "P_1") (pintype "passive"))
      (node (ref "R23") (pin "1") (pinfunction "1_1") (pintype "passive"))
    )
    (net (code "45") (name "Net-(IC3A-H)") (class "Default")
      (node (ref "IC3") (pin "6") (pinfunction "H_6") (pintype "input"))
      (node (ref "PAD24") (pin "1") (pinfunction "P_1") (pintype "passive"))
      (node (ref "R24") (pin "1") (pinfunction "1_1") (pintype "passive"))
    )
    (net (code "46") (name "Net-(IC3A-SER)") (class "Default")
      (node (ref "IC3") (pin "10") (pinfunction "SER_10") (pintype "input"))
      (node (ref "SERIE2") (pin "1") (pinfunction "P_1") (pintype "passive"))
    )
    (net (code "47") (name "Net-(IC3A-SH{slash}~{LD})") (class "Default")
      (node (ref "IC3") (pin "1") (pinfunction "SH/~{LD}_1") (pintype "input"))
      (node (ref "LOAD2") (pin "1") (pinfunction "P_1") (pintype "passive"))
    )
    (net (code "48") (name "Net-(IC4A-A)") (class "Default")
      (node (ref "IC4") (pin "11") (pinfunction "A_11") (pintype "input"))
      (node (ref "PAD25") (pin "1") (pinfunction "P_1") (pintype "passive"))
      (node (ref "R25") (pin "1") (pinfunction "1_1") (pintype "passive"))
    )
    (net (code "49") (name "Net-(IC4A-B)") (class "Default")
      (node (ref "IC4") (pin "12") (pinfunction "B_12") (pintype "input"))
      (node (ref "PAD26") (pin "1") (pinfunction "P_1") (pintype "passive"))
      (node (ref "R26") (pin "1") (pinfunction "1_1") (pintype "passive"))
    )
    (net (code "50") (name "Net-(IC4A-C)") (class "Default")
      (node (ref "IC4") (pin "13") (pinfunction "C_13") (pintype "input"))
      (node (ref "PAD27") (pin "1") (pinfunction "P_1") (pintype "passive"))
      (node (ref "R27") (pin "1") (pinfunction "1_1") (pintype "passive"))
    )
    (net (code "51") (name "Net-(IC4A-CLK)") (class "Default")
      (node (ref "IC4") (pin "2") (pinfunction "CLK_2") (pintype "input"))
      (node (ref "RELOJ3") (pin "1") (pinfunction "P_1") (pintype "passive"))
    )
    (net (code "52") (name "Net-(IC4A-D)") (class "Default")
      (node (ref "IC4") (pin "14") (pinfunction "D_14") (pintype "input"))
      (node (ref "PAD28") (pin "1") (pinfunction "P_1") (pintype "passive"))
      (node (ref "R28") (pin "1") (pinfunction "1_1") (pintype "passive"))
    )
    (net (code "53") (name "Net-(IC4A-E)") (class "Default")
      (node (ref "IC4") (pin "3") (pinfunction "E_3") (pintype "input"))
      (node (ref "PAD29") (pin "1") (pinfunction "P_1") (pintype "passive"))
      (node (ref "R29") (pin "1") (pinfunction "1_1") (pintype "passive"))
    )
    (net (code "54") (name "Net-(IC4A-F)") (class "Default")
      (node (ref "IC4") (pin "4") (pinfunction "F_4") (pintype "input"))
      (node (ref "PAD30") (pin "1") (pinfunction "P_1") (pintype "passive"))
      (node (ref "R30") (pin "1") (pinfunction "1_1") (pintype "passive"))
    )
    (net (code "55") (name "Net-(IC4A-G)") (class "Default")
      (node (ref "IC4") (pin "5") (pinfunction "G_5") (pintype "input"))
      (node (ref "PAD31") (pin "1") (pinfunction "P_1") (pintype "passive"))
      (node (ref "R31") (pin "1") (pinfunction "1_1") (pintype "passive"))
    )
    (net (code "56") (name "Net-(IC4A-H)") (class "Default")
      (node (ref "IC4") (pin "6") (pinfunction "H_6") (pintype "input"))
      (node (ref "PAD32") (pin "1") (pinfunction "P_1") (pintype "passive"))
      (node (ref "R32") (pin "1") (pinfunction "1_1") (pintype "passive"))
    )
    (net (code "57") (name "Net-(IC4A-SER)") (class "Default")
      (node (ref "IC4") (pin "10") (pinfunction "SER_10") (pintype "input"))
      (node (ref "SERIE3") (pin "1") (pinfunction "P_1") (pintype "passive"))
    )
    (net (code "58") (name "Net-(IC4A-SH{slash}~{LD})") (class "Default")
      (node (ref "IC4") (pin "1") (pinfunction "SH/~{LD}_1") (pintype "input"))
      (node (ref "LOAD3") (pin "1") (pinfunction "P_1") (pintype "passive"))
    )
    (net (code "59") (name "Net-(IC5A-A)") (class "Default")
      (node (ref "IC5") (pin "11") (pinfunction "A_11") (pintype "input"))
      (node (ref "PAD33") (pin "1") (pinfunction "P_1") (pintype "passive"))
      (node (ref "R33") (pin "1") (pinfunction "1_1") (pintype "passive"))
    )
    (net (code "60") (name "Net-(IC5A-B)") (class "Default")
      (node (ref "IC5") (pin "12") (pinfunction "B_12") (pintype "input"))
      (node (ref "PAD34") (pin "1") (pinfunction "P_1") (pintype "passive"))
      (node (ref "R34") (pin "1") (pinfunction "1_1") (pintype "passive"))
    )
    (net (code "61") (name "Net-(IC5A-C)") (class "Default")
      (node (ref "IC5") (pin "13") (pinfunction "C_13") (pintype "input"))
      (node (ref "PAD35") (pin "1") (pinfunction "P_1") (pintype "passive"))
      (node (ref "R35") (pin "1") (pinfunction "1_1") (pintype "passive"))
    )
    (net (code "62") (name "Net-(IC5A-CLK)") (class "Default")
      (node (ref "IC5") (pin "2") (pinfunction "CLK_2") (pintype "input"))
      (node (ref "RELOJ4") (pin "1") (pinfunction "P_1") (pintype "passive"))
    )
    (net (code "63") (name "Net-(IC5A-D)") (class "Default")
      (node (ref "IC5") (pin "14") (pinfunction "D_14") (pintype "input"))
      (node (ref "PAD36") (pin "1") (pinfunction "P_1") (pintype "passive"))
      (node (ref "R36") (pin "1") (pinfunction "1_1") (pintype "passive"))
    )
    (net (code "64") (name "Net-(IC5A-E)") (class "Default")
      (node (ref "IC5") (pin "3") (pinfunction "E_3") (pintype "input"))
      (node (ref "PAD37") (pin "1") (pinfunction "P_1") (pintype "passive"))
      (node (ref "R37") (pin "1") (pinfunction "1_1") (pintype "passive"))
    )
    (net (code "65") (name "Net-(IC5A-F)") (class "Default")
      (node (ref "IC5") (pin "4") (pinfunction "F_4") (pintype "input"))
      (node (ref "PAD38") (pin "1") (pinfunction "P_1") (pintype "passive"))
      (node (ref "R38") (pin "1") (pinfunction "1_1") (pintype "passive"))
    )
    (net (code "66") (name "Net-(IC5A-G)") (class "Default")
      (node (ref "IC5") (pin "5") (pinfunction "G_5") (pintype "input"))
      (node (ref "PAD39") (pin "1") (pinfunction "P_1") (pintype "passive"))
      (node (ref "R39") (pin "1") (pinfunction "1_1") (pintype "passive"))
    )
    (net (code "67") (name "Net-(IC5A-H)") (class "Default")
      (node (ref "IC5") (pin "6") (pinfunction "H_6") (pintype "input"))
      (node (ref "PAD40") (pin "1") (pinfunction "P_1") (pintype "passive"))
      (node (ref "R40") (pin "1") (pinfunction "1_1") (pintype "passive"))
    )
    (net (code "68") (name "Net-(IC5A-SER)") (class "Default")
      (node (ref "IC5") (pin "10") (pinfunction "SER_10") (pintype "input"))
      (node (ref "SERIE4") (pin "1") (pinfunction "P_1") (pintype "passive"))
    )
    (net (code "69") (name "Net-(IC5A-SH{slash}~{LD})") (class "Default")
      (node (ref "IC5") (pin "1") (pinfunction "SH/~{LD}_1") (pintype "input"))
      (node (ref "LOAD4") (pin "1") (pinfunction "P_1") (pintype "passive"))
    )
    (net (code "70") (name "Net-(IC6A-A)") (class "Default")
      (node (ref "IC6") (pin "11") (pinfunction "A_11") (pintype "input"))
      (node (ref "PAD41") (pin "1") (pinfunction "P_1") (pintype "passive"))
      (node (ref "R41") (pin "1") (pinfunction "1_1") (pintype "passive"))
    )
    (net (code "71") (name "Net-(IC6A-B)") (class "Default")
      (node (ref "IC6") (pin "12") (pinfunction "B_12") (pintype "input"))
      (node (ref "PAD42") (pin "1") (pinfunction "P_1") (pintype "passive"))
      (node (ref "R42") (pin "1") (pinfunction "1_1") (pintype "passive"))
    )
    (net (code "72") (name "Net-(IC6A-C)") (class "Default")
      (node (ref "IC6") (pin "13") (pinfunction "C_13") (pintype "input"))
      (node (ref "PAD43") (pin "1") (pinfunction "P_1") (pintype "passive"))
      (node (ref "R43") (pin "1") (pinfunction "1_1") (pintype "passive"))
    )
    (net (code "73") (name "Net-(IC6A-CLK)") (class "Default")
      (node (ref "IC6") (pin "2") (pinfunction "CLK_2") (pintype "input"))
      (node (ref "RELOJ5") (pin "1") (pinfunction "P_1") (pintype "passive"))
    )
    (net (code "74") (name "Net-(IC6A-D)") (class "Default")
      (node (ref "IC6") (pin "14") (pinfunction "D_14") (pintype "input"))
      (node (ref "PAD44") (pin "1") (pinfunction "P_1") (pintype "passive"))
      (node (ref "R44") (pin "1") (pinfunction "1_1") (pintype "passive"))
    )
    (net (code "75") (name "Net-(IC6A-E)") (class "Default")
      (node (ref "IC6") (pin "3") (pinfunction "E_3") (pintype "input"))
      (node (ref "PAD45") (pin "1") (pinfunction "P_1") (pintype "passive"))
      (node (ref "R45") (pin "1") (pinfunction "1_1") (pintype "passive"))
    )
    (net (code "76") (name "Net-(IC6A-F)") (class "Default")
      (node (ref "IC6") (pin "4") (pinfunction "F_4") (pintype "input"))
      (node (ref "PAD46") (pin "1") (pinfunction "P_1") (pintype "passive"))
      (node (ref "R46") (pin "1") (pinfunction "1_1") (pintype "passive"))
    )
    (net (code "77") (name "Net-(IC6A-G)") (class "Default")
      (node (ref "IC6") (pin "5") (pinfunction "G_5") (pintype "input"))
      (node (ref "PAD47") (pin "1") (pinfunction "P_1") (pintype "passive"))
      (node (ref "R47") (pin "1") (pinfunction "1_1") (pintype "passive"))
    )
    (net (code "78") (name "Net-(IC6A-H)") (class "Default")
      (node (ref "IC6") (pin "6") (pinfunction "H_6") (pintype "input"))
      (node (ref "PAD48") (pin "1") (pinfunction "P_1") (pintype "passive"))
      (node (ref "R48") (pin "1") (pinfunction "1_1") (pintype "passive"))
    )
    (net (code "79") (name "Net-(IC6A-SH{slash}~{LD})") (class "Default")
      (node (ref "IC6") (pin "1") (pinfunction "SH/~{LD}_1") (pintype "input"))
      (node (ref "LOAD5") (pin "1") (pinfunction "P_1") (pintype "passive"))
    )
    (net (code "80") (name "unconnected-(IC1A-~{QH}-Pad7)") (class "Default")
      (node (ref "IC1") (pin "7") (pinfunction "~{QH}_7") (pintype "output"))
    )
    (net (code "81") (name "unconnected-(IC2A-~{QH}-Pad7)") (class "Default")
      (node (ref "IC2") (pin "7") (pinfunction "~{QH}_7") (pintype "output"))
    )
    (net (code "82") (name "unconnected-(IC3A-~{QH}-Pad7)") (class "Default")
      (node (ref "IC3") (pin "7") (pinfunction "~{QH}_7") (pintype "output"))
    )
    (net (code "83") (name "unconnected-(IC4A-~{QH}-Pad7)") (class "Default")
      (node (ref "IC4") (pin "7") (pinfunction "~{QH}_7") (pintype "output"))
    )
    (net (code "84") (name "unconnected-(IC5A-~{QH}-Pad7)") (class "Default")
      (node (ref "IC5") (pin "7") (pinfunction "~{QH}_7") (pintype "output"))
    )
    (net (code "85") (name "unconnected-(IC6A-SER-Pad10)") (class "Default")
      (node (ref "IC6") (pin "10") (pinfunction "SER_10") (pintype "input"))
    )
    (net (code "86") (name "unconnected-(IC6A-~{QH}-Pad7)") (class "Default")
      (node (ref "IC6") (pin "7") (pinfunction "~{QH}_7") (pintype "output"))
    )
  )
)
